# VRM_Schematic.net
KiCad netlist of a schematic drawn in Altium Designer
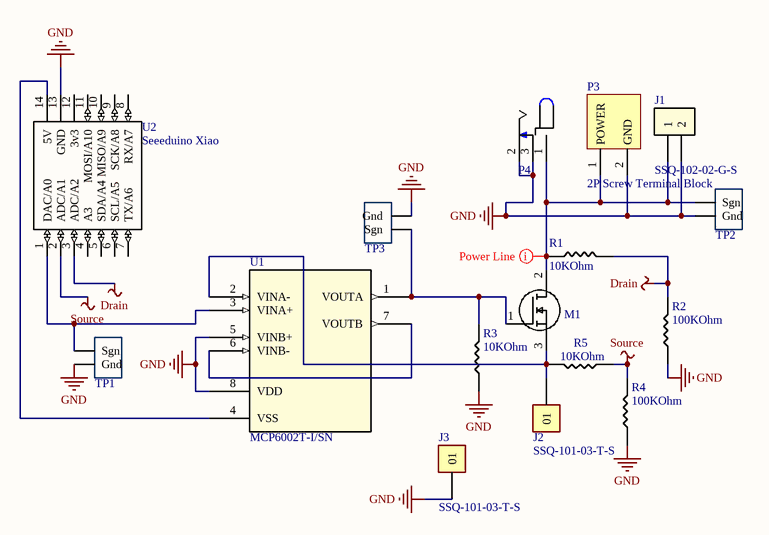
[diagram p0: VRM_Schematic.SchDoc]

(export (version "E")
  (design (tool "Eeschema 10.0.6"))
  (components
    (comp (ref "J1")
      (value "SSQ-102-02-G-S")
      (footprint "JF-2_1X2_TU_SSQ")
      (description "2.54mm Straight 1x2P 2 1 Straight,P=2.54mm  Female Headers ROHSon Available")
      (fields (field (name "MFR PART #") "C49661"))
      (libsource (lib "ECEN5730Lib_2023_05_DS") (part "JF_2_PIN_FEMALE"))
    )
    (comp (ref "J2")
      (value "SSQ-101-03-T-S")
      (footprint "JF-1_SSQ-101-03-T-S")
      (description "SSQ Series .100 Tiger Buyâ„¢ Socket Strip, Square Tail")
      (fields (field (name "MFR PART #") "X6511FV-01-C85D32") (field (name "LCSC PART#") "C2883837"))
      (libsource (lib "ECEN5730Lib_2023_05_DS") (part "JF_1_PIN_FEMALE"))
    )
    (comp (ref "J3")
      (value "SSQ-101-03-T-S")
      (footprint "JF-1_SSQ-101-03-T-S")
      (description "SSQ Series .100 Tiger Buyâ„¢ Socket Strip, Square Tail")
      (fields (field (name "MFR PART #") "X6511FV-01-C85D32") (field (name "LCSC PART#") "C2883837"))
      (libsource (lib "") (part "JF_1_PIN_FEMALE_1"))
    )
    (comp (ref "M1")
      (value "IRL520NPBF")
      (footprint "TO254P469X1042X1967-3P")
      (description "MOSFET (N-Channel)  IRL520NPBF")
      (fields (field (name "MOUSER PART NUMBER") "942-IRL520NPBF"))
      (libsource (lib "ECEN5730Lib_2023_05_DS") (part "Q_Nch_MOSFET_PTH"))
    )
    (comp (ref "P3")
      (value "2P Screw Terminal Block")
      (footprint "P_Terminal block 3.5mm-pitch")
      (description "Green Straight pin 3.5mm  pitch; P=3.5mm  Screw terminal ROHS")
      (fields (field (name "MFR PART #") "KF350-3.5-2P") (field (name "MANUFACTURER") "Cixi Kefa Elec"))
      (libsource (lib "ECEN5730Lib_2023_05_DS") (part "P_Terminal block"))
    )
    (comp (ref "P4")
      (value "Power Jack")
      (footprint "Power_Jack")
      (description "Power Barrel Connector Jack 2.10mm ID (0.083\"), 5.50mm OD (0.217\") Through Hole, Right Angle")
      (fields (field (name "MFR PART #") "PJ-102A") (field (name "LCSC PART#") "C136744"))
      (libsource (lib "ECEN5730Lib_2023_05_DS") (part "P_Power Jack"))
    )
    (comp (ref "R1")
      (value "10KOhm")
      (footprint "1206_Passive_Resitor")
      (description "10 kOhms ±5% 0.25W, 1/4W Chip Resistor 1206 (3216 Metric) Automotive AEC-Q200 Thick Film")
      (fields (field (name "MFR PART #") "RMCF1206FT10K0") (field (name "LCSC PART#") "C17902"))
      (libsource (lib "ECEN5730Lib_2023_05_DS") (part "R_10KOhm_1206"))
    )
    (comp (ref "R2")
      (value "100KOhm")
      (footprint "1206_Passive_Resitor")
      (description "100kΩ ±1% 0.25W ±100ppm/℃ 1206 Chip Resistor - Surface Mount RoHS")
      (fields (field (name "LCSC PART#") "C17900") (field (name "MFR PART #") "1206W4F1003T5E"))
      (libsource (lib "ECEN5730Lib_2023_05_DS") (part "R_100KOhm_1206"))
    )
    (comp (ref "R3")
      (value "10KOhm")
      (footprint "1206_Passive_Resitor")
      (description "10 kOhms ±5% 0.25W, 1/4W Chip Resistor 1206 (3216 Metric) Automotive AEC-Q200 Thick Film")
      (fields (field (name "MFR PART #") "RMCF1206FT10K0") (field (name "LCSC PART#") "C17902"))
      (libsource (lib "ECEN5730Lib_2023_05_DS") (part "R_10KOhm_1206"))
    )
    (comp (ref "R4")
      (value "100KOhm")
      (footprint "1206_Passive_Resitor")
      (description "100kΩ ±1% 0.25W ±100ppm/℃ 1206 Chip Resistor - Surface Mount RoHS")
      (fields (field (name "LCSC PART#") "C17900") (field (name "MFR PART #") "1206W4F1003T5E"))
      (libsource (lib "ECEN5730Lib_2023_05_DS") (part "R_100KOhm_1206"))
    )
    (comp (ref "R5")
      (value "10KOhm")
      (footprint "1206_Passive_Resitor")
      (description "10 kOhms ±5% 0.25W, 1/4W Chip Resistor 1206 (3216 Metric) Automotive AEC-Q200 Thick Film")
      (fields (field (name "LCSC PART#") "C17902") (field (name "MFR PART #") "RMCF1206FT10K0"))
      (libsource (lib "ECEN5730Lib_2023_05_DS") (part "R_10KOhm_1206"))
    )
    (comp (ref "TP1")
      (value "10x Probe TP")
      (footprint "TP10x_Probe")
      (description "Test Point 300 mil centers")
      (libsource (lib "") (part "TP_10x_Probe_1"))
    )
    (comp (ref "TP2")
      (value "10x Probe TP")
      (footprint "TP10x_Probe")
      (description "Test Point 300 mil centers")
      (libsource (lib "") (part "TP_10x_Probe_1"))
    )
    (comp (ref "TP3")
      (value "10x Probe TP")
      (footprint "TP10x_Probe")
      (description "Test Point 300 mil centers")
      (libsource (lib "ECEN5730Lib_2023_05_DS") (part "TP_10x_Probe"))
    )
    (comp (ref "U1")
      (value "MCP6002T-I/SN")
      (footprint "SOIC127P600X175-8N")
      (description "0.6 V/us 2 1MHz 1.8V ~ 6V 100μA General Purpose SOIC-8_150mil  Operational Amplifier ROHS")
      (fields (field (name "MFR") "Microchip") (field (name "LCSC PART#") "C7377"))
      (libsource (lib "ECEN5730Lib_2023_05_DS") (part "U_MCP6002T-I/SN"))
    )
    (comp (ref "U2")
      (value "Seeeduino Xiao")
      (footprint "SAMD21_Xiao")
      (description "Seeeduino XIAO - Arduino Microcontroller - SAMD21 Cortex M0+")
      (libsource (lib "ECEN5730Lib_Manual_2022_07LibPkg") (part "U_SAMD21_Xiao"))
    )
  )
  (nets
    (net (code "1") (name "Drain") (class "Default")
      (node (ref "R1") (pin "2") (pinfunction "2_2") (pintype "passive"))
      (node (ref "R2") (pin "2") (pinfunction "2_2") (pintype "passive"))
      (node (ref "U2") (pin "3") (pinfunction "ADC/A2_3") (pintype "bidirectional"))
    )
    (net (code "2") (name "GND") (class "Default")
      (node (ref "J1") (pin "2") (pinfunction "2_2") (pintype "passive"))
      (node (ref "J3") (pin "01") (pinfunction "01_01") (pintype "passive"))
      (node (ref "P3") (pin "2") (pinfunction "GND_2") (pintype "passive"))
      (node (ref "P4") (pin "2") (pinfunction "2_2") (pintype "power_in"))
      (node (ref "P4") (pin "3") (pinfunction "3_3") (pintype "power_in"))
      (node (ref "R2") (pin "1") (pinfunction "1_1") (pintype "passive"))
      (node (ref "R3") (pin "1") (pinfunction "1_1") (pintype "passive"))
      (node (ref "R4") (pin "1") (pinfunction "1_1") (pintype "passive"))
      (node (ref "TP1") (pin "2") (pinfunction "Gnd_2") (pintype "passive"))
      (node (ref "TP2") (pin "2") (pinfunction "Gnd_2") (pintype "passive"))
      (node (ref "TP3") (pin "2") (pinfunction "Gnd_2") (pintype "passive"))
      (node (ref "U1") (pin "5") (pinfunction "VINB+_5") (pintype "input"))
      (node (ref "U1") (pin "8") (pinfunction "VDD_8") (pintype "passive"))
      (node (ref "U2") (pin "13") (pinfunction "GND_13") (pintype "power_in"))
    )
    (net (code "3") (name "Net-(M1-D)") (class "Default")
      (node (ref "J1") (pin "1") (pinfunction "1_1") (pintype "passive"))
      (node (ref "M1") (pin "2") (pinfunction "D_2") (pintype "passive"))
      (node (ref "P3") (pin "1") (pinfunction "POWER_1") (pintype "passive"))
      (node (ref "P4") (pin "1") (pinfunction "1_1") (pintype "power_in"))
      (node (ref "R1") (pin "1") (pinfunction "1_1") (pintype "passive"))
      (node (ref "TP2") (pin "1") (pinfunction "Sgn_1") (pintype "passive"))
    )
    (net (code "4") (name "Net-(M1-G)") (class "Default")
      (node (ref "M1") (pin "1") (pinfunction "G_1") (pintype "passive"))
      (node (ref "R3") (pin "2") (pinfunction "2_2") (pintype "passive"))
      (node (ref "TP3") (pin "1") (pinfunction "Sgn_1") (pintype "passive"))
      (node (ref "U1") (pin "1") (pinfunction "VOUTA_1") (pintype "output"))
    )
    (net (code "5") (name "Net-(M1-S)") (class "Default")
      (node (ref "J2") (pin "01") (pinfunction "01_01") (pintype "passive"))
      (node (ref "M1") (pin "3") (pinfunction "S_3") (pintype "passive"))
      (node (ref "R5") (pin "2") (pinfunction "2_2") (pintype "passive"))
      (node (ref "U1") (pin "2") (pinfunction "VINA-_2") (pintype "input"))
    )
    (net (code "6") (name "Net-(TP1-Sgn)") (class "Default")
      (node (ref "TP1") (pin "1") (pinfunction "Sgn_1") (pintype "passive"))
      (node (ref "U1") (pin "3") (pinfunction "VINA+_3") (pintype "input"))
      (node (ref "U2") (pin "1") (pinfunction "DAC/A0_1") (pintype "bidirectional"))
    )
    (net (code "7") (name "Net-(U1-VINB-)") (class "Default")
      (node (ref "U1") (pin "6") (pinfunction "VINB-_6") (pintype "input"))
      (node (ref "U1") (pin "7") (pinfunction "VOUTB_7") (pintype "output"))
    )
    (net (code "8") (name "Net-(U1-VSS)") (class "Default")
      (node (ref "U1") (pin "4") (pinfunction "VSS_4") (pintype "passive"))
      (node (ref "U2") (pin "14") (pinfunction "5V_14") (pintype "power_in"))
    )
    (net (code "9") (name "Source") (class "Default")
      (node (ref "R4") (pin "2") (pinfunction "2_2") (pintype "passive"))
      (node (ref "R5") (pin "1") (pinfunction "1_1") (pintype "passive"))
      (node (ref "U2") (pin "2") (pinfunction "ADC/A1_2") (pintype "bidirectional"))
    )
    (net (code "10") (name "unconnected-(U2-3v3-Pad12)") (class "Default")
      (node (ref "U2") (pin "12") (pinfunction "3v3_12") (pintype "power_in"))
    )
    (net (code "11") (name "unconnected-(U2-A3-Pad4)") (class "Default")
      (node (ref "U2") (pin "4") (pinfunction "A3_4") (pintype "bidirectional"))
    )
    (net (code "12") (name "unconnected-(U2-MISO{slash}A9-Pad10)") (class "Default")
      (node (ref "U2") (pin "10") (pinfunction "MISO/A9_10") (pintype "bidirectional"))
    )
    (net (code "13") (name "unconnected-(U2-MOSI{slash}A10-Pad11)") (class "Default")
      (node (ref "U2") (pin "11") (pinfunction "MOSI/A10_11") (pintype "bidirectional"))
    )
    (net (code "14") (name "unconnected-(U2-RX{slash}A7-Pad8)") (class "Default")
      (node (ref "U2") (pin "8") (pinfunction "RX/A7_8") (pintype "bidirectional"))
    )
    (net (code "15") (name "unconnected-(U2-SCK{slash}A8-Pad9)") (class "Default")
      (node (ref "U2") (pin "9") (pinfunction "SCK/A8_9") (pintype "bidirectional"))
    )
    (net (code "16") (name "unconnected-(U2-SCL{slash}A5-Pad6)") (class "Default")
      (node (ref "U2") (pin "6") (pinfunction "SCL/A5_6") (pintype "bidirectional"))
    )
    (net (code "17") (name "unconnected-(U2-SDA{slash}A4-Pad5)") (class "Default")
      (node (ref "U2") (pin "5") (pinfunction "SDA/A4_5") (pintype "bidirectional"))
    )
    (net (code "18") (name "unconnected-(U2-TX{slash}A6-Pad7)") (class "Default")
      (node (ref "U2") (pin "7") (pinfunction "TX/A6_7") (pintype "bidirectional"))
    )
  )
)
